# PoE_Injector.net
KiCad netlist of a schematic drawn in Altium Designer
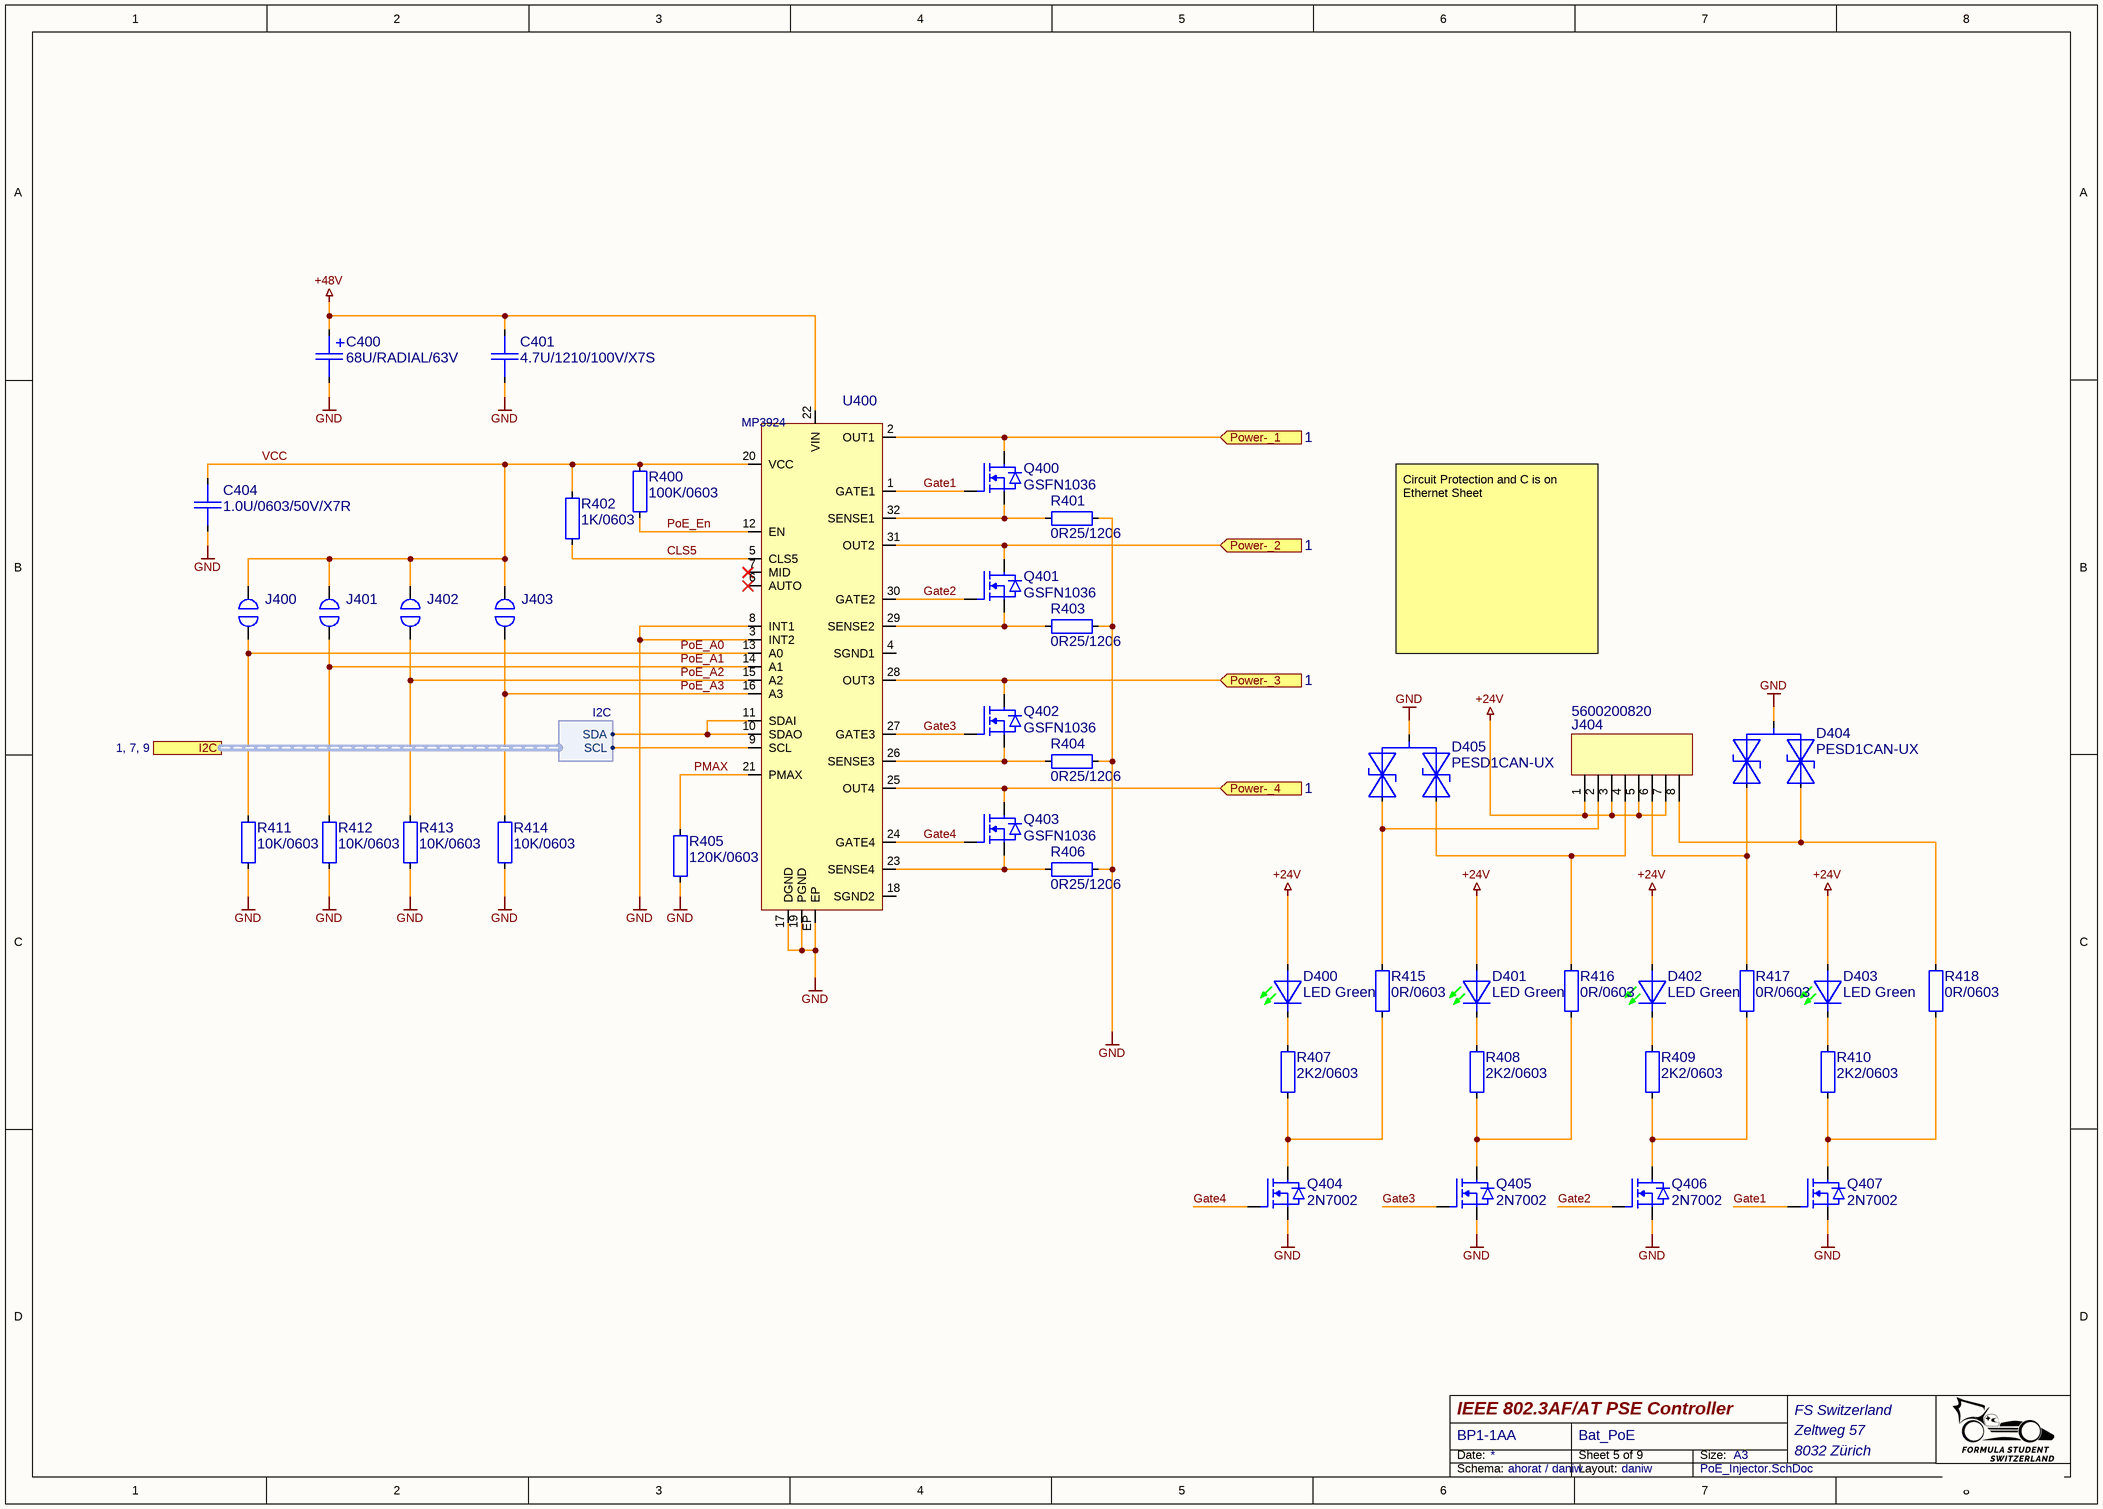
[diagram p0: PoE_Injector.SchDoc]

(export (version "E")
  (design (tool "Eeschema 10.0.6"))
  (components
    (comp (ref "C400")
      (value "68U/RADIAL/63V")
      (footprint "CAP350P80X130")
      (description "CAP THT 8C130 68UF ELKO 63V")
      (fields (field (name "MANUFACTURER") "GENERIC"))
      (libsource (lib "daniw_altium_lib") (part "C_ELEC"))
    )
    (comp (ref "C401")
      (value "4.7U/1210/100V/X7S")
      (footprint "CAP1210_X7R")
      (description "CAP SM 1210 4.7uF 100V X7S")
      (fields (field (name "MANUFACTURER") "GENERIC"))
      (libsource (lib "daniw_altium_lib") (part "C"))
    )
    (comp (ref "C404")
      (value "1.0U/0603/50V/X7R")
      (footprint "CAP0603_X7R")
      (description "CAP SM 0603 1.0uF 50V X7R")
      (fields (field (name "MANUFACTURER") "GENERIC"))
      (libsource (lib "daniw_altium_lib") (part "C"))
    )
    (comp (ref "D400")
      (value "LED Green")
      (footprint "LED0603_GREEN")
      (description "Generic LED Green 0603")
      (fields (field (name "PART NUMBER") "LED Green 0603") (field (name "MANUFACTURER") "GENERIC"))
      (libsource (lib "daniw_altium_lib") (part "LED_GREEN"))
    )
    (comp (ref "D401")
      (value "LED Green")
      (footprint "LED0603_GREEN")
      (description "Generic LED Green 0603")
      (fields (field (name "PART NUMBER") "LED Green 0603") (field (name "MANUFACTURER") "GENERIC"))
      (libsource (lib "daniw_altium_lib") (part "LED_GREEN"))
    )
    (comp (ref "D402")
      (value "LED Green")
      (footprint "LED0603_GREEN")
      (description "Generic LED Green 0603")
      (fields (field (name "PART NUMBER") "LED Green 0603") (field (name "MANUFACTURER") "GENERIC"))
      (libsource (lib "daniw_altium_lib") (part "LED_GREEN"))
    )
    (comp (ref "D403")
      (value "LED Green")
      (footprint "LED0603_GREEN")
      (description "Generic LED Green 0603")
      (fields (field (name "PART NUMBER") "LED Green 0603") (field (name "MANUFACTURER") "GENERIC"))
      (libsource (lib "daniw_altium_lib") (part "LED_GREEN"))
    )
    (comp (ref "D404")
      (value "PESD1CAN-UX")
      (footprint "SOT65P210X95-3-SE")
      (description "CAN bus ESD protection diode")
      (fields (field (name "MANUFACTURER") "Nexperia USA Inc."))
      (libsource (lib "daniw_altium_lib") (part "D_TVS_BIDIR_DUAL"))
    )
    (comp (ref "D405")
      (value "PESD1CAN-UX")
      (footprint "SOT65P210X95-3-SE")
      (description "CAN bus ESD protection diode")
      (fields (field (name "MANUFACTURER") "Nexperia USA Inc."))
      (libsource (lib "daniw_altium_lib") (part "D_TVS_BIDIR_DUAL"))
    )
    (comp (ref "J400")
      (value "Solder Jumper 2pin 0.2mm small")
      (footprint "Solder_Jumper_2pin_0.2mm_small")
      (description "Solder jumper with two pins with a spacing of 0.2mm")
      (fields
        (field (name "PART NUMBER") "Solder_Jumper_2pin_0.2mm_small")
        (field (name "MANUFACTURER") "NONE")
      )
      (libsource (lib "daniw_altium_lib") (part "SolderJumper_2"))
    )
    (comp (ref "J401")
      (value "Solder Jumper 2pin 0.2mm small")
      (footprint "Solder_Jumper_2pin_0.2mm_small")
      (description "Solder jumper with two pins with a spacing of 0.2mm")
      (fields
        (field (name "PART NUMBER") "Solder_Jumper_2pin_0.2mm_small")
        (field (name "MANUFACTURER") "NONE")
      )
      (libsource (lib "daniw_altium_lib") (part "SolderJumper_2"))
    )
    (comp (ref "J402")
      (value "Solder Jumper 2pin 0.2mm small")
      (footprint "Solder_Jumper_2pin_0.2mm_small")
      (description "Solder jumper with two pins with a spacing of 0.2mm")
      (fields
        (field (name "PART NUMBER") "Solder_Jumper_2pin_0.2mm_small")
        (field (name "MANUFACTURER") "NONE")
      )
      (libsource (lib "daniw_altium_lib") (part "SolderJumper_2"))
    )
    (comp (ref "J403")
      (value "Solder Jumper 2pin 0.2mm small")
      (footprint "Solder_Jumper_2pin_0.2mm_small")
      (description "Solder jumper with two pins with a spacing of 0.2mm")
      (fields
        (field (name "PART NUMBER") "Solder_Jumper_2pin_0.2mm_small")
        (field (name "MANUFACTURER") "NONE")
      )
      (libsource (lib "daniw_altium_lib") (part "SolderJumper_2"))
    )
    (comp (ref "J404")
      (value "5600200820")
      (footprint "5600200820")
      (description "DuraClik Wire-to-Board Header, Single Row, Vertical, 8 Circuits, Tin (Sn) Over Nickel, Natural")
      (fields (field (name "PART NUMBER") "DuraClick_1x8_VERT_SMD") (field (name "MANUFACTURER") "Molex"))
      (libsource (lib "daniw_altium_lib") (part "CON8"))
    )
    (comp (ref "Q400")
      (value "GSFN1036")
      (footprint "SON065P330X330X075-5-TH245X175")
      (description "N-Kanal 100 V 35 A (Tc) 52W (Tc) Oberflächenmontage 8-PPAK (3,1x3,05)")
      (fields (field (name "MANUFACTURER") "Good-Ark Semiconductor"))
      (libsource (lib "daniw_altium_lib") (part "MOSFET N"))
    )
    (comp (ref "Q401")
      (value "GSFN1036")
      (footprint "SON065P330X330X075-5-TH245X175")
      (description "N-Kanal 100 V 35 A (Tc) 52W (Tc) Oberflächenmontage 8-PPAK (3,1x3,05)")
      (fields (field (name "MANUFACTURER") "Good-Ark Semiconductor"))
      (libsource (lib "daniw_altium_lib") (part "MOSFET N"))
    )
    (comp (ref "Q402")
      (value "GSFN1036")
      (footprint "SON065P330X330X075-5-TH245X175")
      (description "N-Kanal 100 V 35 A (Tc) 52W (Tc) Oberflächenmontage 8-PPAK (3,1x3,05)")
      (fields (field (name "MANUFACTURER") "Good-Ark Semiconductor"))
      (libsource (lib "daniw_altium_lib") (part "MOSFET N"))
    )
    (comp (ref "Q403")
      (value "GSFN1036")
      (footprint "SON065P330X330X075-5-TH245X175")
      (description "N-Kanal 100 V 35 A (Tc) 52W (Tc) Oberflächenmontage 8-PPAK (3,1x3,05)")
      (fields (field (name "MANUFACTURER") "Good-Ark Semiconductor"))
      (libsource (lib "daniw_altium_lib") (part "MOSFET N"))
    )
    (comp (ref "Q404")
      (value "2N7002")
      (footprint "SOT2395P280X125-3-SE")
      (description "60V 115mA 1.2Ω@10V,500mA 200mW 2.1V@250uA N Channel SOT-23 MOSFETs")
      (fields (field (name "MANUFACTURER") "GENERIC"))
      (libsource (lib "daniw_altium_lib") (part "MOSFET N_SOT23"))
    )
    (comp (ref "Q405")
      (value "2N7002")
      (footprint "SOT2395P280X125-3-SE")
      (description "60V 115mA 1.2Ω@10V,500mA 200mW 2.1V@250uA N Channel SOT-23 MOSFETs")
      (fields (field (name "MANUFACTURER") "GENERIC"))
      (libsource (lib "daniw_altium_lib") (part "MOSFET N_SOT23"))
    )
    (comp (ref "Q406")
      (value "2N7002")
      (footprint "SOT2395P280X125-3-SE")
      (description "60V 115mA 1.2Ω@10V,500mA 200mW 2.1V@250uA N Channel SOT-23 MOSFETs")
      (fields (field (name "MANUFACTURER") "GENERIC"))
      (libsource (lib "daniw_altium_lib") (part "MOSFET N_SOT23"))
    )
    (comp (ref "Q407")
      (value "2N7002")
      (footprint "SOT2395P280X125-3-SE")
      (description "60V 115mA 1.2Ω@10V,500mA 200mW 2.1V@250uA N Channel SOT-23 MOSFETs")
      (fields (field (name "MANUFACTURER") "GENERIC"))
      (libsource (lib "daniw_altium_lib") (part "MOSFET N_SOT23"))
    )
    (comp (ref "R400")
      (value "100K/0603")
      (footprint "R0603-0.40-WW")
      (description "RES SM 0603 100K")
      (fields (field (name "MANUFACTURER") "GENERIC"))
      (libsource (lib "daniw_altium_lib") (part "R"))
    )
    (comp (ref "R401")
      (value "0R25/1206")
      (footprint "R1206-0.80-WW")
      (description "RES SM 1206 0R25")
      (fields (field (name "MANUFACTURER") "GENERIC"))
      (libsource (lib "daniw_altium_lib") (part "R"))
    )
    (comp (ref "R402")
      (value "1K/0603")
      (footprint "R0603-0.40-WW")
      (description "RES SM 0603 1K")
      (fields (field (name "MANUFACTURER") "GENERIC"))
      (libsource (lib "daniw_altium_lib") (part "R"))
    )
    (comp (ref "R403")
      (value "0R25/1206")
      (footprint "R1206-0.80-WW")
      (description "RES SM 1206 0R25")
      (fields (field (name "MANUFACTURER") "GENERIC"))
      (libsource (lib "daniw_altium_lib") (part "R"))
    )
    (comp (ref "R404")
      (value "0R25/1206")
      (footprint "R1206-0.80-WW")
      (description "RES SM 1206 0R25")
      (fields (field (name "MANUFACTURER") "GENERIC"))
      (libsource (lib "daniw_altium_lib") (part "R"))
    )
    (comp (ref "R405")
      (value "120K/0603")
      (footprint "R0603-0.40-WW")
      (description "RES SM 0603 120K")
      (fields (field (name "MANUFACTURER") "GENERIC"))
      (libsource (lib "daniw_altium_lib") (part "R"))
    )
    (comp (ref "R406")
      (value "0R25/1206")
      (footprint "R1206-0.80-WW")
      (description "RES SM 1206 0R25")
      (fields (field (name "MANUFACTURER") "GENERIC"))
      (libsource (lib "daniw_altium_lib") (part "R"))
    )
    (comp (ref "R407")
      (value "2K2/0603")
      (footprint "R0603-0.40-WW")
      (description "RES SM 0603 2K2")
      (fields (field (name "MANUFACTURER") "GENERIC"))
      (libsource (lib "daniw_altium_lib") (part "R"))
    )
    (comp (ref "R408")
      (value "2K2/0603")
      (footprint "R0603-0.40-WW")
      (description "RES SM 0603 2K2")
      (fields (field (name "MANUFACTURER") "GENERIC"))
      (libsource (lib "daniw_altium_lib") (part "R"))
    )
    (comp (ref "R409")
      (value "2K2/0603")
      (footprint "R0603-0.40-WW")
      (description "RES SM 0603 2K2")
      (fields (field (name "MANUFACTURER") "GENERIC"))
      (libsource (lib "daniw_altium_lib") (part "R"))
    )
    (comp (ref "R410")
      (value "2K2/0603")
      (footprint "R0603-0.40-WW")
      (description "RES SM 0603 2K2")
      (fields (field (name "MANUFACTURER") "GENERIC"))
      (libsource (lib "daniw_altium_lib") (part "R"))
    )
    (comp (ref "R411")
      (value "10K/0603")
      (footprint "R0603-0.40-WW")
      (description "RES SM 0603 10K")
      (fields (field (name "MANUFACTURER") "GENERIC"))
      (libsource (lib "daniw_altium_lib") (part "R"))
    )
    (comp (ref "R412")
      (value "10K/0603")
      (footprint "R0603-0.40-WW")
      (description "RES SM 0603 10K")
      (fields (field (name "MANUFACTURER") "GENERIC"))
      (libsource (lib "daniw_altium_lib") (part "R"))
    )
    (comp (ref "R413")
      (value "10K/0603")
      (footprint "R0603-0.40-WW")
      (description "RES SM 0603 10K")
      (fields (field (name "MANUFACTURER") "GENERIC"))
      (libsource (lib "daniw_altium_lib") (part "R"))
    )
    (comp (ref "R414")
      (value "10K/0603")
      (footprint "R0603-0.40-WW")
      (description "RES SM 0603 10K")
      (fields (field (name "MANUFACTURER") "GENERIC"))
      (libsource (lib "daniw_altium_lib") (part "R"))
    )
    (comp (ref "R415")
      (value "0R/0603")
      (footprint "R0603-0.40-WW")
      (description "RES SM 0603 0R")
      (fields (field (name "MANUFACTURER") "GENERIC"))
      (libsource (lib "daniw_altium_lib") (part "R"))
    )
    (comp (ref "R416")
      (value "0R/0603")
      (footprint "R0603-0.40-WW")
      (description "RES SM 0603 0R")
      (fields (field (name "MANUFACTURER") "GENERIC"))
      (libsource (lib "daniw_altium_lib") (part "R"))
    )
    (comp (ref "R417")
      (value "0R/0603")
      (footprint "R0603-0.40-WW")
      (description "RES SM 0603 0R")
      (fields (field (name "MANUFACTURER") "GENERIC"))
      (libsource (lib "daniw_altium_lib") (part "R"))
    )
    (comp (ref "R418")
      (value "0R/0603")
      (footprint "R0603-0.40-WW")
      (description "RES SM 0603 0R")
      (fields (field (name "MANUFACTURER") "GENERIC"))
      (libsource (lib "daniw_altium_lib") (part "R"))
    )
    (comp (ref "U400")
      (value "MP3924")
      (footprint "QFN050P500X500X100-32-TH360X360")
      (description "Quad-Port, IEEE 802.3af/at PSE Controller for Power over Ethernet")
      (fields (field (name "MANUFACTURER") "MPS"))
      (libsource (lib "daniw_altium_lib") (part "MP3924"))
    )
  )
  (nets
    (net (code "2") (name "+24V") (class "Default")
      (node (ref "D400") (pin "2") (pinfunction "2_2") (pintype "passive"))
      (node (ref "D401") (pin "2") (pinfunction "2_2") (pintype "passive"))
      (node (ref "D402") (pin "2") (pinfunction "2_2") (pintype "passive"))
      (node (ref "D403") (pin "2") (pinfunction "2_2") (pintype "passive"))
      (node (ref "J404") (pin "1") (pintype "passive"))
      (node (ref "J404") (pin "3") (pintype "passive"))
      (node (ref "J404") (pin "5") (pintype "passive"))
      (node (ref "J404") (pin "7") (pintype "passive"))
    )
    (net (code "3") (name "+48V") (class "Default")
      (node (ref "C400") (pin "1") (pinfunction "1_1") (pintype "passive"))
      (node (ref "C401") (pin "1") (pinfunction "1_1") (pintype "passive"))
      (node (ref "U400") (pin "22") (pinfunction "VIN_22") (pintype "passive"))
    )
    (net (code "4") (name "/CLS5") (class "Default")
      (node (ref "R402") (pin "2") (pinfunction "2_2") (pintype "passive"))
      (node (ref "U400") (pin "5") (pinfunction "CLS5_5") (pintype "passive"))
    )
    (net (code "5") (name "/Gate1") (class "Default")
      (node (ref "Q400") (pin "G") (pinfunction "GATE_G") (pintype "passive"))
      (node (ref "Q407") (pin "1") (pinfunction "GATE_1") (pintype "passive"))
      (node (ref "U400") (pin "1") (pinfunction "GATE1_1") (pintype "passive"))
    )
    (net (code "6") (name "/Gate2") (class "Default")
      (node (ref "Q401") (pin "G") (pinfunction "GATE_G") (pintype "passive"))
      (node (ref "Q406") (pin "1") (pinfunction "GATE_1") (pintype "passive"))
      (node (ref "U400") (pin "30") (pinfunction "GATE2_30") (pintype "passive"))
    )
    (net (code "7") (name "/Gate3") (class "Default")
      (node (ref "Q402") (pin "G") (pinfunction "GATE_G") (pintype "passive"))
      (node (ref "Q405") (pin "1") (pinfunction "GATE_1") (pintype "passive"))
      (node (ref "U400") (pin "27") (pinfunction "GATE3_27") (pintype "passive"))
    )
    (net (code "8") (name "/Gate4") (class "Default")
      (node (ref "Q403") (pin "G") (pinfunction "GATE_G") (pintype "passive"))
      (node (ref "Q404") (pin "1") (pinfunction "GATE_1") (pintype "passive"))
      (node (ref "U400") (pin "24") (pinfunction "GATE4_24") (pintype "passive"))
    )
    (net (code "9") (name "/PMAX") (class "Default")
      (node (ref "R405") (pin "1") (pinfunction "1_1") (pintype "passive"))
      (node (ref "U400") (pin "21") (pinfunction "PMAX_21") (pintype "passive"))
    )
    (net (code "10") (name "/PoE_A0") (class "Default")
      (node (ref "J400") (pin "2") (pinfunction "2_2") (pintype "passive"))
      (node (ref "R411") (pin "1") (pinfunction "1_1") (pintype "passive"))
      (node (ref "U400") (pin "13") (pinfunction "A0_13") (pintype "passive"))
    )
    (net (code "11") (name "/PoE_A1") (class "Default")
      (node (ref "J401") (pin "2") (pinfunction "2_2") (pintype "passive"))
      (node (ref "R412") (pin "1") (pinfunction "1_1") (pintype "passive"))
      (node (ref "U400") (pin "14") (pinfunction "A1_14") (pintype "passive"))
    )
    (net (code "12") (name "/PoE_A2") (class "Default")
      (node (ref "J402") (pin "2") (pinfunction "2_2") (pintype "passive"))
      (node (ref "R413") (pin "1") (pinfunction "1_1") (pintype "passive"))
      (node (ref "U400") (pin "15") (pinfunction "A2_15") (pintype "passive"))
    )
    (net (code "13") (name "/PoE_A3") (class "Default")
      (node (ref "J403") (pin "2") (pinfunction "2_2") (pintype "passive"))
      (node (ref "R414") (pin "1") (pinfunction "1_1") (pintype "passive"))
      (node (ref "U400") (pin "16") (pinfunction "A3_16") (pintype "passive"))
    )
    (net (code "14") (name "/PoE_En") (class "Default")
      (node (ref "R400") (pin "2") (pinfunction "2_2") (pintype "passive"))
      (node (ref "U400") (pin "12") (pinfunction "EN_12") (pintype "passive"))
    )
    (net (code "15") (name "/Power-_1") (class "Default")
      (node (ref "Q400") (pin "D") (pinfunction "DRAIN_D") (pintype "passive"))
      (node (ref "U400") (pin "2") (pinfunction "OUT1_2") (pintype "passive"))
    )
    (net (code "16") (name "/Power-_2") (class "Default")
      (node (ref "Q401") (pin "D") (pinfunction "DRAIN_D") (pintype "passive"))
      (node (ref "U400") (pin "31") (pinfunction "OUT2_31") (pintype "passive"))
    )
    (net (code "17") (name "/Power-_3") (class "Default")
      (node (ref "Q402") (pin "D") (pinfunction "DRAIN_D") (pintype "passive"))
      (node (ref "U400") (pin "28") (pinfunction "OUT3_28") (pintype "passive"))
    )
    (net (code "18") (name "/Power-_4") (class "Default")
      (node (ref "Q403") (pin "D") (pinfunction "DRAIN_D") (pintype "passive"))
      (node (ref "U400") (pin "25") (pinfunction "OUT4_25") (pintype "passive"))
    )
    (net (code "19") (name "/SCL") (class "Default")
      (node (ref "U400") (pin "9") (pinfunction "SCL_9") (pintype "passive"))
    )
    (net (code "20") (name "/SDA") (class "Default")
      (node (ref "U400") (pin "10") (pinfunction "SDAO_10") (pintype "passive"))
      (node (ref "U400") (pin "11") (pinfunction "SDAI_11") (pintype "passive"))
    )
    (net (code "21") (name "/VCC") (class "Default")
      (node (ref "C404") (pin "1") (pinfunction "1_1") (pintype "passive"))
      (node (ref "J400") (pin "1") (pinfunction "1_1") (pintype "passive"))
      (node (ref "J401") (pin "1") (pinfunction "1_1") (pintype "passive"))
      (node (ref "J402") (pin "1") (pinfunction "1_1") (pintype "passive"))
      (node (ref "J403") (pin "1") (pinfunction "1_1") (pintype "passive"))
      (node (ref "R400") (pin "1") (pinfunction "1_1") (pintype "passive"))
      (node (ref "R402") (pin "1") (pinfunction "1_1") (pintype "passive"))
      (node (ref "U400") (pin "20") (pinfunction "VCC_20") (pintype "passive"))
    )
    (net (code "23") (name "GND") (class "Default")
      (node (ref "C400") (pin "2") (pinfunction "2_2") (pintype "passive"))
      (node (ref "C401") (pin "2") (pinfunction "2_2") (pintype "passive"))
      (node (ref "C404") (pin "2") (pinfunction "2_2") (pintype "passive"))
      (node (ref "D404") (pin "3") (pinfunction "3_3") (pintype "passive"))
      (node (ref "D405") (pin "3") (pinfunction "3_3") (pintype "passive"))
      (node (ref "Q404") (pin "2") (pinfunction "SOURCE_2") (pintype "passive"))
      (node (ref "Q405") (pin "2") (pinfunction "SOURCE_2") (pintype "passive"))
      (node (ref "Q406") (pin "2") (pinfunction "SOURCE_2") (pintype "passive"))
      (node (ref "Q407") (pin "2") (pinfunction "SOURCE_2") (pintype "passive"))
      (node (ref "R401") (pin "2") (pinfunction "2_2") (pintype "passive"))
      (node (ref "R403") (pin "2") (pinfunction "2_2") (pintype "passive"))
      (node (ref "R404") (pin "2") (pinfunction "2_2") (pintype "passive"))
      (node (ref "R405") (pin "2") (pinfunction "2_2") (pintype "passive"))
      (node (ref "R406") (pin "2") (pinfunction "2_2") (pintype "passive"))
      (node (ref "R411") (pin "2") (pinfunction "2_2") (pintype "passive"))
      (node (ref "R412") (pin "2") (pinfunction "2_2") (pintype "passive"))
      (node (ref "R413") (pin "2") (pinfunction "2_2") (pintype "passive"))
      (node (ref "R414") (pin "2") (pinfunction "2_2") (pintype "passive"))
      (node (ref "U400") (pin "17") (pinfunction "DGND_17") (pintype "passive"))
      (node (ref "U400") (pin "19") (pinfunction "PGND_19") (pintype "passive"))
      (node (ref "U400") (pin "3") (pinfunction "INT2_3") (pintype "passive"))
      (node (ref "U400") (pin "8") (pinfunction "INT1_8") (pintype "passive"))
      (node (ref "U400") (pin "EP") (pinfunction "EP_EP") (pintype "passive"))
    )
    (net (code "24") (name "Net-(D400-Pad1)") (class "Default")
      (node (ref "D400") (pin "1") (pinfunction "1_1") (pintype "passive"))
      (node (ref "R407") (pin "1") (pinfunction "1_1") (pintype "passive"))
    )
    (net (code "25") (name "Net-(D401-Pad1)") (class "Default")
      (node (ref "D401") (pin "1") (pinfunction "1_1") (pintype "passive"))
      (node (ref "R408") (pin "1") (pinfunction "1_1") (pintype "passive"))
    )
    (net (code "26") (name "Net-(D402-Pad1)") (class "Default")
      (node (ref "D402") (pin "1") (pinfunction "1_1") (pintype "passive"))
      (node (ref "R409") (pin "1") (pinfunction "1_1") (pintype "passive"))
    )
    (net (code "27") (name "Net-(D403-Pad1)") (class "Default")
      (node (ref "D403") (pin "1") (pinfunction "1_1") (pintype "passive"))
      (node (ref "R410") (pin "1") (pinfunction "1_1") (pintype "passive"))
    )
    (net (code "28") (name "Net-(D404-Pad1)") (class "Default")
      (node (ref "D404") (pin "1") (pinfunction "1_1") (pintype "passive"))
      (node (ref "J404") (pin "8") (pintype "passive"))
      (node (ref "R418") (pin "1") (pinfunction "1_1") (pintype "passive"))
    )
    (net (code "29") (name "Net-(D404-Pad2)") (class "Default")
      (node (ref "D404") (pin "2") (pinfunction "2_2") (pintype "passive"))
      (node (ref "J404") (pin "6") (pintype "passive"))
      (node (ref "R417") (pin "1") (pinfunction "1_1") (pintype "passive"))
    )
    (net (code "30") (name "Net-(D405-Pad1)") (class "Default")
      (node (ref "D405") (pin "1") (pinfunction "1_1") (pintype "passive"))
      (node (ref "J404") (pin "4") (pintype "passive"))
      (node (ref "R416") (pin "1") (pinfunction "1_1") (pintype "passive"))
    )
    (net (code "31") (name "Net-(D405-Pad2)") (class "Default")
      (node (ref "D405") (pin "2") (pinfunction "2_2") (pintype "passive"))
      (node (ref "J404") (pin "2") (pintype "passive"))
      (node (ref "R415") (pin "1") (pinfunction "1_1") (pintype "passive"))
    )
    (net (code "32") (name "Net-(Q400-SOURCE)") (class "Default")
      (node (ref "Q400") (pin "S") (pinfunction "SOURCE_S") (pintype "passive"))
      (node (ref "R401") (pin "1") (pinfunction "1_1") (pintype "passive"))
      (node (ref "U400") (pin "32") (pinfunction "SENSE1_32") (pintype "passive"))
    )
    (net (code "33") (name "Net-(Q401-SOURCE)") (class "Default")
      (node (ref "Q401") (pin "S") (pinfunction "SOURCE_S") (pintype "passive"))
      (node (ref "R403") (pin "1") (pinfunction "1_1") (pintype "passive"))
      (node (ref "U400") (pin "29") (pinfunction "SENSE2_29") (pintype "passive"))
    )
    (net (code "34") (name "Net-(Q402-SOURCE)") (class "Default")
      (node (ref "Q402") (pin "S") (pinfunction "SOURCE_S") (pintype "passive"))
      (node (ref "R404") (pin "1") (pinfunction "1_1") (pintype "passive"))
      (node (ref "U400") (pin "26") (pinfunction "SENSE3_26") (pintype "passive"))
    )
    (net (code "35") (name "Net-(Q403-SOURCE)") (class "Default")
      (node (ref "Q403") (pin "S") (pinfunction "SOURCE_S") (pintype "passive"))
      (node (ref "R406") (pin "1") (pinfunction "1_1") (pintype "passive"))
      (node (ref "U400") (pin "23") (pinfunction "SENSE4_23") (pintype "passive"))
    )
    (net (code "36") (name "Net-(Q404-DRAIN)") (class "Default")
      (node (ref "Q404") (pin "3") (pinfunction "DRAIN_3") (pintype "passive"))
      (node (ref "R407") (pin "2") (pinfunction "2_2") (pintype "passive"))
      (node (ref "R415") (pin "2") (pinfunction "2_2") (pintype "passive"))
    )
    (net (code "37") (name "Net-(Q405-DRAIN)") (class "Default")
      (node (ref "Q405") (pin "3") (pinfunction "DRAIN_3") (pintype "passive"))
      (node (ref "R408") (pin "2") (pinfunction "2_2") (pintype "passive"))
      (node (ref "R416") (pin "2") (pinfunction "2_2") (pintype "passive"))
    )
    (net (code "38") (name "Net-(Q406-DRAIN)") (class "Default")
      (node (ref "Q406") (pin "3") (pinfunction "DRAIN_3") (pintype "passive"))
      (node (ref "R409") (pin "2") (pinfunction "2_2") (pintype "passive"))
      (node (ref "R417") (pin "2") (pinfunction "2_2") (pintype "passive"))
    )
    (net (code "39") (name "Net-(Q407-DRAIN)") (class "Default")
      (node (ref "Q407") (pin "3") (pinfunction "DRAIN_3") (pintype "passive"))
      (node (ref "R410") (pin "2") (pinfunction "2_2") (pintype "passive"))
      (node (ref "R418") (pin "2") (pinfunction "2_2") (pintype "passive"))
    )
    (net (code "40") (name "unconnected-(U400-AUTO-Pad6)") (class "Default")
      (node (ref "U400") (pin "6") (pinfunction "AUTO_6") (pintype "passive+no_connect"))
    )
    (net (code "41") (name "unconnected-(U400-MID-Pad7)") (class "Default")
      (node (ref "U400") (pin "7") (pinfunction "MID_7") (pintype "passive+no_connect"))
    )
    (net (code "42") (name "unconnected-(U400-SGND1-Pad4)") (class "Default")
      (node (ref "U400") (pin "4") (pinfunction "SGND1_4") (pintype "passive"))
    )
    (net (code "43") (name "unconnected-(U400-SGND2-Pad18)") (class "Default")
      (node (ref "U400") (pin "18") (pinfunction "SGND2_18") (pintype "passive"))
    )
  )
)
